# Power_Board.net
KiCad netlist of a schematic drawn in Altium Designer
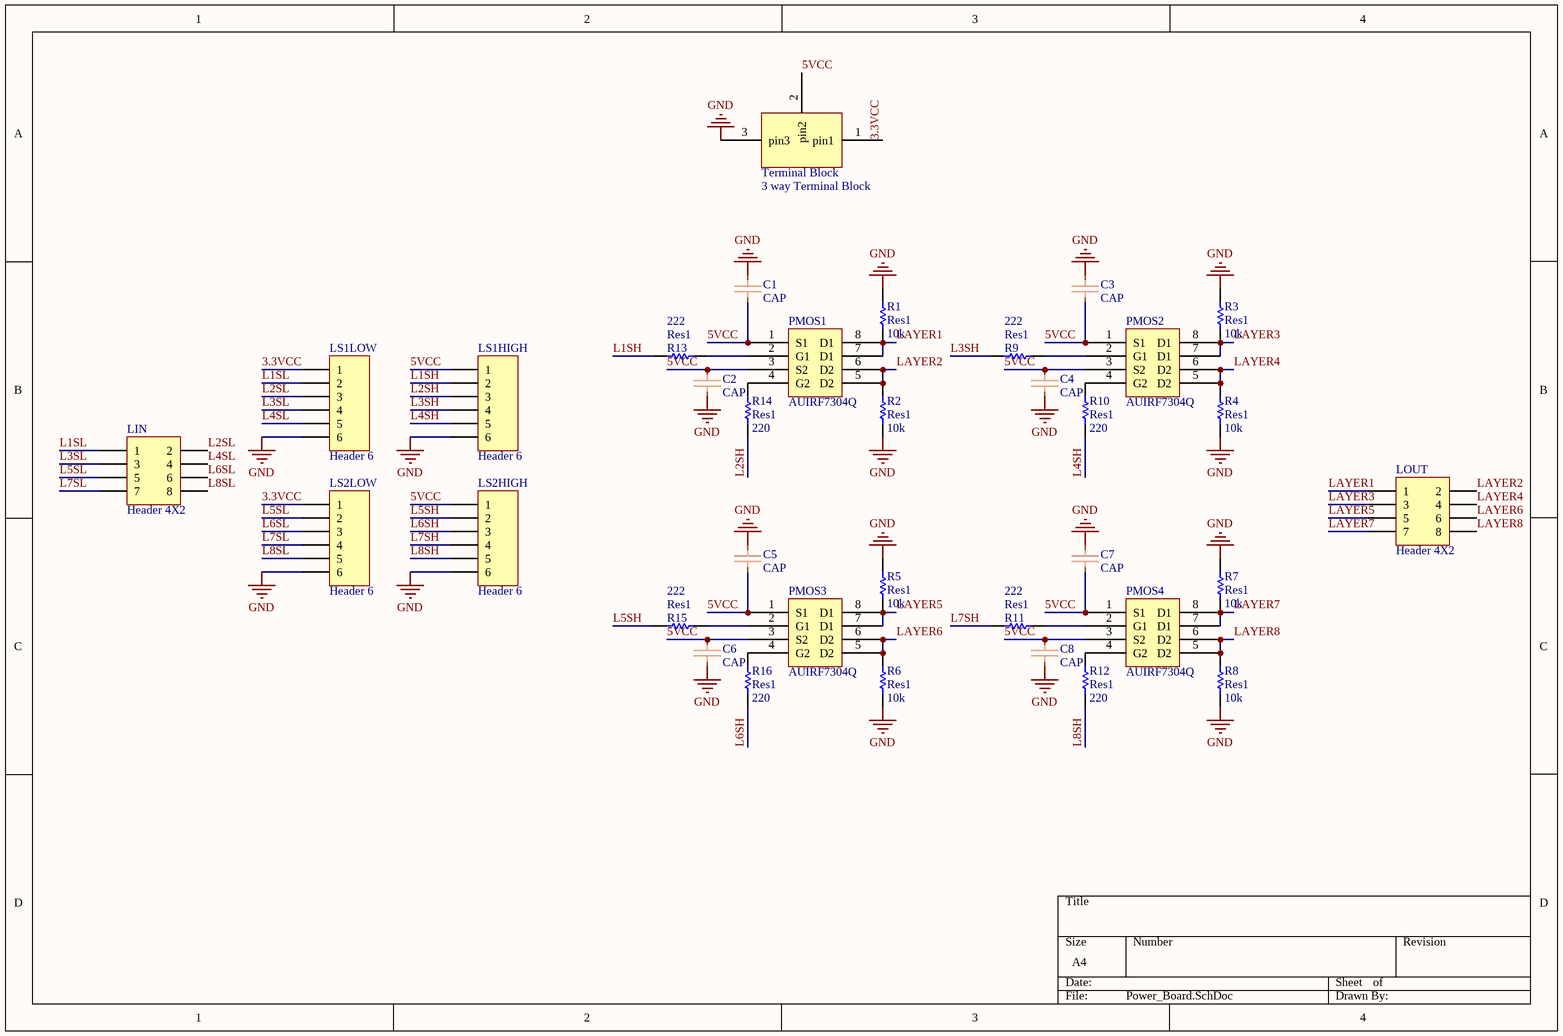
[diagram p0: Power_Board.SchDoc]

(export (version "E")
  (design (tool "Eeschema 10.0.6"))
  (components
    (comp (ref "C1")
      (value "CAP")
      (footprint "RAD0.2A")
      (description "Capacitor")
      (libsource (lib "KBsch01") (part "CAP"))
    )
    (comp (ref "C2")
      (value "CAP")
      (footprint "RAD0.2A")
      (description "Capacitor")
      (libsource (lib "KBsch01") (part "CAP"))
    )
    (comp (ref "C3")
      (value "CAP")
      (footprint "RAD0.2A")
      (description "Capacitor")
      (libsource (lib "KBsch01") (part "CAP"))
    )
    (comp (ref "C4")
      (value "CAP")
      (footprint "RAD0.2A")
      (description "Capacitor")
      (libsource (lib "KBsch01") (part "CAP"))
    )
    (comp (ref "C5")
      (value "CAP")
      (footprint "RAD0.2A")
      (description "Capacitor")
      (libsource (lib "KBsch01") (part "CAP"))
    )
    (comp (ref "C6")
      (value "CAP")
      (footprint "RAD0.2A")
      (description "Capacitor")
      (libsource (lib "KBsch01") (part "CAP"))
    )
    (comp (ref "C7")
      (value "CAP")
      (footprint "RAD0.2A")
      (description "Capacitor")
      (libsource (lib "KBsch01") (part "CAP"))
    )
    (comp (ref "C8")
      (value "CAP")
      (footprint "RAD0.2A")
      (description "Capacitor")
      (libsource (lib "KBsch01") (part "CAP"))
    )
    (comp (ref "LIN")
      (value "Header 4X2")
      (footprint "HDR2X4")
      (description "Header, 4-Pin, Dual row")
      (fields (field (name "PUBLISHER") "Altium Limited"))
      (libsource (lib "Miscellaneous Connectors") (part "Header 4X2"))
    )
    (comp (ref "LOUT")
      (value "Header 4X2")
      (footprint "HDR2X4")
      (description "Header, 4-Pin, Dual row")
      (fields (field (name "PUBLISHER") "Altium Limited"))
      (libsource (lib "Miscellaneous Connectors") (part "Header 4X2"))
    )
    (comp (ref "LS1HIGH")
      (value "Header 6")
      (footprint "HDR1X6")
      (description "Header, 6-Pin")
      (fields (field (name "PUBLISHER") "Altium Limited"))
      (libsource (lib "Miscellaneous Connectors") (part "Header 6"))
    )
    (comp (ref "LS1LOW")
      (value "Header 6")
      (footprint "HDR1X6")
      (description "Header, 6-Pin")
      (fields (field (name "PUBLISHER") "Altium Limited"))
      (libsource (lib "Miscellaneous Connectors") (part "Header 6"))
    )
    (comp (ref "LS2HIGH")
      (value "Header 6")
      (footprint "HDR1X6")
      (description "Header, 6-Pin")
      (fields (field (name "PUBLISHER") "Altium Limited"))
      (libsource (lib "Miscellaneous Connectors") (part "Header 6"))
    )
    (comp (ref "LS2LOW")
      (value "Header 6")
      (footprint "HDR1X6")
      (description "Header, 6-Pin")
      (fields (field (name "PUBLISHER") "Altium Limited"))
      (libsource (lib "Miscellaneous Connectors") (part "Header 6"))
    )
    (comp (ref "PMOS1")
      (value "AUIRF7304Q")
      (footprint "AUIRF7304Q")
      (libsource (lib "AUIRF7304Q") (part "Component_1"))
    )
    (comp (ref "PMOS2")
      (value "AUIRF7304Q")
      (footprint "AUIRF7304Q")
      (libsource (lib "AUIRF7304Q") (part "Component_1"))
    )
    (comp (ref "PMOS3")
      (value "AUIRF7304Q")
      (footprint "AUIRF7304Q")
      (libsource (lib "AUIRF7304Q") (part "Component_1"))
    )
    (comp (ref "PMOS4")
      (value "AUIRF7304Q")
      (footprint "AUIRF7304Q")
      (libsource (lib "AUIRF7304Q") (part "Component_1"))
    )
    (comp (ref "R1")
      (value "Res1")
      (footprint "AXIAL0.4")
      (description "Resistor")
      (fields (field (name "ALTIUM_VALUE") "10k") (field (name "PUBLISHER") "Altium Limited"))
      (libsource (lib "Miscellaneous Devices") (part "Res1"))
    )
    (comp (ref "R2")
      (value "Res1")
      (footprint "AXIAL0.4")
      (description "Resistor")
      (fields (field (name "ALTIUM_VALUE") "10k") (field (name "PUBLISHER") "Altium Limited"))
      (libsource (lib "Miscellaneous Devices") (part "Res1"))
    )
    (comp (ref "R3")
      (value "Res1")
      (footprint "AXIAL0.4")
      (description "Resistor")
      (fields (field (name "ALTIUM_VALUE") "10k") (field (name "PUBLISHER") "Altium Limited"))
      (libsource (lib "Miscellaneous Devices") (part "Res1"))
    )
    (comp (ref "R4")
      (value "Res1")
      (footprint "AXIAL0.4")
      (description "Resistor")
      (fields (field (name "ALTIUM_VALUE") "10k") (field (name "PUBLISHER") "Altium Limited"))
      (libsource (lib "Miscellaneous Devices") (part "Res1"))
    )
    (comp (ref "R5")
      (value "Res1")
      (footprint "AXIAL0.4")
      (description "Resistor")
      (fields (field (name "ALTIUM_VALUE") "10k") (field (name "PUBLISHER") "Altium Limited"))
      (libsource (lib "Miscellaneous Devices") (part "Res1"))
    )
    (comp (ref "R6")
      (value "Res1")
      (footprint "AXIAL0.4")
      (description "Resistor")
      (fields (field (name "ALTIUM_VALUE") "10k") (field (name "PUBLISHER") "Altium Limited"))
      (libsource (lib "Miscellaneous Devices") (part "Res1"))
    )
    (comp (ref "R7")
      (value "Res1")
      (footprint "AXIAL0.4")
      (description "Resistor")
      (fields (field (name "ALTIUM_VALUE") "10k") (field (name "PUBLISHER") "Altium Limited"))
      (libsource (lib "Miscellaneous Devices") (part "Res1"))
    )
    (comp (ref "R8")
      (value "Res1")
      (footprint "AXIAL0.4")
      (description "Resistor")
      (fields (field (name "ALTIUM_VALUE") "10k") (field (name "PUBLISHER") "Altium Limited"))
      (libsource (lib "Miscellaneous Devices") (part "Res1"))
    )
    (comp (ref "R9")
      (value "Res1")
      (footprint "AXIAL0.4")
      (description "Resistor")
      (fields (field (name "ALTIUM_VALUE") "222") (field (name "PUBLISHER") "Altium Limited"))
      (libsource (lib "Miscellaneous Devices") (part "Res1"))
    )
    (comp (ref "R10")
      (value "Res1")
      (footprint "AXIAL0.4")
      (description "Resistor")
      (fields (field (name "ALTIUM_VALUE") "220") (field (name "PUBLISHER") "Altium Limited"))
      (libsource (lib "Miscellaneous Devices") (part "Res1"))
    )
    (comp (ref "R11")
      (value "Res1")
      (footprint "AXIAL0.4")
      (description "Resistor")
      (fields (field (name "ALTIUM_VALUE") "222") (field (name "PUBLISHER") "Altium Limited"))
      (libsource (lib "Miscellaneous Devices") (part "Res1"))
    )
    (comp (ref "R12")
      (value "Res1")
      (footprint "AXIAL0.4")
      (description "Resistor")
      (fields (field (name "ALTIUM_VALUE") "220") (field (name "PUBLISHER") "Altium Limited"))
      (libsource (lib "Miscellaneous Devices") (part "Res1"))
    )
    (comp (ref "R13")
      (value "Res1")
      (footprint "AXIAL0.4")
      (description "Resistor")
      (fields (field (name "ALTIUM_VALUE") "222") (field (name "PUBLISHER") "Altium Limited"))
      (libsource (lib "Miscellaneous Devices") (part "Res1"))
    )
    (comp (ref "R14")
      (value "Res1")
      (footprint "AXIAL0.4")
      (description "Resistor")
      (fields (field (name "ALTIUM_VALUE") "220") (field (name "PUBLISHER") "Altium Limited"))
      (libsource (lib "Miscellaneous Devices") (part "Res1"))
    )
    (comp (ref "R15")
      (value "Res1")
      (footprint "AXIAL0.4")
      (description "Resistor")
      (fields (field (name "ALTIUM_VALUE") "222") (field (name "PUBLISHER") "Altium Limited"))
      (libsource (lib "Miscellaneous Devices") (part "Res1"))
    )
    (comp (ref "R16")
      (value "Res1")
      (footprint "AXIAL0.4")
      (description "Resistor")
      (fields (field (name "ALTIUM_VALUE") "220") (field (name "PUBLISHER") "Altium Limited"))
      (libsource (lib "Miscellaneous Devices") (part "Res1"))
    )
    (comp (ref "Terminal Block")
      (value "3 way Terminal Block")
      (footprint "PCTB3N")
      (libsource (lib "Terminal Block") (part "Component_1"))
    )
  )
  (nets
    (net (code "1") (name "/3.3VCC") (class "Default")
      (node (ref "LS1LOW") (pin "1") (pinfunction "1_1") (pintype "passive"))
      (node (ref "LS2LOW") (pin "1") (pinfunction "1_1") (pintype "passive"))
      (node (ref "Terminal Block") (pin "1") (pinfunction "pin1_1") (pintype "passive"))
    )
    (net (code "2") (name "/5VCC") (class "Default")
      (node (ref "C1") (pin "2") (pinfunction "N/A_2") (pintype "passive"))
      (node (ref "C2") (pin "1") (pinfunction "N/A_1") (pintype "passive"))
      (node (ref "C3") (pin "2") (pinfunction "N/A_2") (pintype "passive"))
      (node (ref "C4") (pin "1") (pinfunction "N/A_1") (pintype "passive"))
      (node (ref "C5") (pin "2") (pinfunction "N/A_2") (pintype "passive"))
      (node (ref "C6") (pin "1") (pinfunction "N/A_1") (pintype "passive"))
      (node (ref "C7") (pin "2") (pinfunction "N/A_2") (pintype "passive"))
      (node (ref "C8") (pin "1") (pinfunction "N/A_1") (pintype "passive"))
      (node (ref "LS1HIGH") (pin "1") (pinfunction "1_1") (pintype "passive"))
      (node (ref "LS2HIGH") (pin "1") (pinfunction "1_1") (pintype "passive"))
      (node (ref "PMOS1") (pin "1") (pinfunction "S1_1") (pintype "passive"))
      (node (ref "PMOS1") (pin "3") (pinfunction "S2_3") (pintype "passive"))
      (node (ref "PMOS2") (pin "1") (pinfunction "S1_1") (pintype "passive"))
      (node (ref "PMOS2") (pin "3") (pinfunction "S2_3") (pintype "passive"))
      (node (ref "PMOS3") (pin "1") (pinfunction "S1_1") (pintype "passive"))
      (node (ref "PMOS3") (pin "3") (pinfunction "S2_3") (pintype "passive"))
      (node (ref "PMOS4") (pin "1") (pinfunction "S1_1") (pintype "passive"))
      (node (ref "PMOS4") (pin "3") (pinfunction "S2_3") (pintype "passive"))
      (node (ref "Terminal Block") (pin "2") (pinfunction "pin2_2") (pintype "passive"))
    )
    (net (code "3") (name "/L1SH") (class "Default")
      (node (ref "LS1HIGH") (pin "2") (pinfunction "2_2") (pintype "passive"))
      (node (ref "R13") (pin "1") (pinfunction "1_1") (pintype "passive"))
    )
    (net (code "4") (name "/L1SL") (class "Default")
      (node (ref "LIN") (pin "1") (pinfunction "1_1") (pintype "passive"))
      (node (ref "LS1LOW") (pin "2") (pinfunction "2_2") (pintype "passive"))
    )
    (net (code "5") (name "/L2SH") (class "Default")
      (node (ref "LS1HIGH") (pin "3") (pinfunction "3_3") (pintype "passive"))
      (node (ref "R14") (pin "1") (pinfunction "1_1") (pintype "passive"))
    )
    (net (code "6") (name "/L2SL") (class "Default")
      (node (ref "LIN") (pin "2") (pinfunction "2_2") (pintype "passive"))
      (node (ref "LS1LOW") (pin "3") (pinfunction "3_3") (pintype "passive"))
    )
    (net (code "7") (name "/L3SH") (class "Default")
      (node (ref "LS1HIGH") (pin "4") (pinfunction "4_4") (pintype "passive"))
      (node (ref "R9") (pin "1") (pinfunction "1_1") (pintype "passive"))
    )
    (net (code "8") (name "/L3SL") (class "Default")
      (node (ref "LIN") (pin "3") (pinfunction "3_3") (pintype "passive"))
      (node (ref "LS1LOW") (pin "4") (pinfunction "4_4") (pintype "passive"))
    )
    (net (code "9") (name "/L4SH") (class "Default")
      (node (ref "LS1HIGH") (pin "5") (pinfunction "5_5") (pintype "passive"))
      (node (ref "R10") (pin "1") (pinfunction "1_1") (pintype "passive"))
    )
    (net (code "10") (name "/L4SL") (class "Default")
      (node (ref "LIN") (pin "4") (pinfunction "4_4") (pintype "passive"))
      (node (ref "LS1LOW") (pin "5") (pinfunction "5_5") (pintype "passive"))
    )
    (net (code "11") (name "/L5SH") (class "Default")
      (node (ref "LS2HIGH") (pin "2") (pinfunction "2_2") (pintype "passive"))
      (node (ref "R15") (pin "1") (pinfunction "1_1") (pintype "passive"))
    )
    (net (code "12") (name "/L5SL") (class "Default")
      (node (ref "LIN") (pin "5") (pinfunction "5_5") (pintype "passive"))
      (node (ref "LS2LOW") (pin "2") (pinfunction "2_2") (pintype "passive"))
    )
    (net (code "13") (name "/L6SH") (class "Default")
      (node (ref "LS2HIGH") (pin "3") (pinfunction "3_3") (pintype "passive"))
      (node (ref "R16") (pin "1") (pinfunction "1_1") (pintype "passive"))
    )
    (net (code "14") (name "/L6SL") (class "Default")
      (node (ref "LIN") (pin "6") (pinfunction "6_6") (pintype "passive"))
      (node (ref "LS2LOW") (pin "3") (pinfunction "3_3") (pintype "passive"))
    )
    (net (code "15") (name "/L7SH") (class "Default")
      (node (ref "LS2HIGH") (pin "4") (pinfunction "4_4") (pintype "passive"))
      (node (ref "R11") (pin "1") (pinfunction "1_1") (pintype "passive"))
    )
    (net (code "16") (name "/L7SL") (class "Default")
      (node (ref "LIN") (pin "7") (pinfunction "7_7") (pintype "passive"))
      (node (ref "LS2LOW") (pin "4") (pinfunction "4_4") (pintype "passive"))
    )
    (net (code "17") (name "/L8SH") (class "Default")
      (node (ref "LS2HIGH") (pin "5") (pinfunction "5_5") (pintype "passive"))
      (node (ref "R12") (pin "1") (pinfunction "1_1") (pintype "passive"))
    )
    (net (code "18") (name "/L8SL") (class "Default")
      (node (ref "LIN") (pin "8") (pinfunction "8_8") (pintype "passive"))
      (node (ref "LS2LOW") (pin "5") (pinfunction "5_5") (pintype "passive"))
    )
    (net (code "19") (name "/LAYER1") (class "Default")
      (node (ref "LOUT") (pin "1") (pinfunction "1_1") (pintype "passive"))
      (node (ref "PMOS1") (pin "7") (pinfunction "D1_7") (pintype "passive"))
      (node (ref "PMOS1") (pin "8") (pinfunction "D1_8") (pintype "passive"))
      (node (ref "R1") (pin "2") (pinfunction "2_2") (pintype "passive"))
    )
    (net (code "20") (name "/LAYER2") (class "Default")
      (node (ref "LOUT") (pin "2") (pinfunction "2_2") (pintype "passive"))
      (node (ref "PMOS1") (pin "5") (pinfunction "D2_5") (pintype "passive"))
      (node (ref "PMOS1") (pin "6") (pinfunction "D2_6") (pintype "passive"))
      (node (ref "R2") (pin "1") (pinfunction "1_1") (pintype "passive"))
    )
    (net (code "21") (name "/LAYER3") (class "Default")
      (node (ref "LOUT") (pin "3") (pinfunction "3_3") (pintype "passive"))
      (node (ref "PMOS2") (pin "7") (pinfunction "D1_7") (pintype "passive"))
      (node (ref "PMOS2") (pin "8") (pinfunction "D1_8") (pintype "passive"))
      (node (ref "R3") (pin "2") (pinfunction "2_2") (pintype "passive"))
    )
    (net (code "22") (name "/LAYER4") (class "Default")
      (node (ref "LOUT") (pin "4") (pinfunction "4_4") (pintype "passive"))
      (node (ref "PMOS2") (pin "5") (pinfunction "D2_5") (pintype "passive"))
      (node (ref "PMOS2") (pin "6") (pinfunction "D2_6") (pintype "passive"))
      (node (ref "R4") (pin "1") (pinfunction "1_1") (pintype "passive"))
    )
    (net (code "23") (name "/LAYER5") (class "Default")
      (node (ref "LOUT") (pin "5") (pinfunction "5_5") (pintype "passive"))
      (node (ref "PMOS3") (pin "7") (pinfunction "D1_7") (pintype "passive"))
      (node (ref "PMOS3") (pin "8") (pinfunction "D1_8") (pintype "passive"))
      (node (ref "R5") (pin "2") (pinfunction "2_2") (pintype "passive"))
    )
    (net (code "24") (name "/LAYER6") (class "Default")
      (node (ref "LOUT") (pin "6") (pinfunction "6_6") (pintype "passive"))
      (node (ref "PMOS3") (pin "5") (pinfunction "D2_5") (pintype "passive"))
      (node (ref "PMOS3") (pin "6") (pinfunction "D2_6") (pintype "passive"))
      (node (ref "R6") (pin "1") (pinfunction "1_1") (pintype "passive"))
    )
    (net (code "25") (name "/LAYER7") (class "Default")
      (node (ref "LOUT") (pin "7") (pinfunction "7_7") (pintype "passive"))
      (node (ref "PMOS4") (pin "7") (pinfunction "D1_7") (pintype "passive"))
      (node (ref "PMOS4") (pin "8") (pinfunction "D1_8") (pintype "passive"))
      (node (ref "R7") (pin "2") (pinfunction "2_2") (pintype "passive"))
    )
    (net (code "26") (name "/LAYER8") (class "Default")
      (node (ref "LOUT") (pin "8") (pinfunction "8_8") (pintype "passive"))
      (node (ref "PMOS4") (pin "5") (pinfunction "D2_5") (pintype "passive"))
      (node (ref "PMOS4") (pin "6") (pinfunction "D2_6") (pintype "passive"))
      (node (ref "R8") (pin "1") (pinfunction "1_1") (pintype "passive"))
    )
    (net (code "27") (name "GND") (class "Default")
      (node (ref "C1") (pin "1") (pinfunction "N/A_1") (pintype "passive"))
      (node (ref "C2") (pin "2") (pinfunction "N/A_2") (pintype "passive"))
      (node (ref "C3") (pin "1") (pinfunction "N/A_1") (pintype "passive"))
      (node (ref "C4") (pin "2") (pinfunction "N/A_2") (pintype "passive"))
      (node (ref "C5") (pin "1") (pinfunction "N/A_1") (pintype "passive"))
      (node (ref "C6") (pin "2") (pinfunction "N/A_2") (pintype "passive"))
      (node (ref "C7") (pin "1") (pinfunction "N/A_1") (pintype "passive"))
      (node (ref "C8") (pin "2") (pinfunction "N/A_2") (pintype "passive"))
      (node (ref "LS1HIGH") (pin "6") (pinfunction "6_6") (pintype "passive"))
      (node (ref "LS1LOW") (pin "6") (pinfunction "6_6") (pintype "passive"))
      (node (ref "LS2HIGH") (pin "6") (pinfunction "6_6") (pintype "passive"))
      (node (ref "LS2LOW") (pin "6") (pinfunction "6_6") (pintype "passive"))
      (node (ref "R1") (pin "1") (pinfunction "1_1") (pintype "passive"))
      (node (ref "R2") (pin "2") (pinfunction "2_2") (pintype "passive"))
      (node (ref "R3") (pin "1") (pinfunction "1_1") (pintype "passive"))
      (node (ref "R4") (pin "2") (pinfunction "2_2") (pintype "passive"))
      (node (ref "R5") (pin "1") (pinfunction "1_1") (pintype "passive"))
      (node (ref "R6") (pin "2") (pinfunction "2_2") (pintype "passive"))
      (node (ref "R7") (pin "1") (pinfunction "1_1") (pintype "passive"))
      (node (ref "R8") (pin "2") (pinfunction "2_2") (pintype "passive"))
      (node (ref "Terminal Block") (pin "3") (pinfunction "pin3_3") (pintype "passive"))
    )
    (net (code "28") (name "Net-(PMOS1-G1)") (class "Default")
      (node (ref "PMOS1") (pin "2") (pinfunction "G1_2") (pintype "passive"))
      (node (ref "R13") (pin "2") (pinfunction "2_2") (pintype "passive"))
    )
    (net (code "29") (name "Net-(PMOS1-G2)") (class "Default")
      (node (ref "PMOS1") (pin "4") (pinfunction "G2_4") (pintype "passive"))
      (node (ref "R14") (pin "2") (pinfunction "2_2") (pintype "passive"))
    )
    (net (code "30") (name "Net-(PMOS2-G1)") (class "Default")
      (node (ref "PMOS2") (pin "2") (pinfunction "G1_2") (pintype "passive"))
      (node (ref "R9") (pin "2") (pinfunction "2_2") (pintype "passive"))
    )
    (net (code "31") (name "Net-(PMOS2-G2)") (class "Default")
      (node (ref "PMOS2") (pin "4") (pinfunction "G2_4") (pintype "passive"))
      (node (ref "R10") (pin "2") (pinfunction "2_2") (pintype "passive"))
    )
    (net (code "32") (name "Net-(PMOS3-G1)") (class "Default")
      (node (ref "PMOS3") (pin "2") (pinfunction "G1_2") (pintype "passive"))
      (node (ref "R15") (pin "2") (pinfunction "2_2") (pintype "passive"))
    )
    (net (code "33") (name "Net-(PMOS3-G2)") (class "Default")
      (node (ref "PMOS3") (pin "4") (pinfunction "G2_4") (pintype "passive"))
      (node (ref "R16") (pin "2") (pinfunction "2_2") (pintype "passive"))
    )
    (net (code "34") (name "Net-(PMOS4-G1)") (class "Default")
      (node (ref "PMOS4") (pin "2") (pinfunction "G1_2") (pintype "passive"))
      (node (ref "R11") (pin "2") (pinfunction "2_2") (pintype "passive"))
    )
    (net (code "35") (name "Net-(PMOS4-G2)") (class "Default")
      (node (ref "PMOS4") (pin "4") (pinfunction "G2_4") (pintype "passive"))
      (node (ref "R12") (pin "2") (pinfunction "2_2") (pintype "passive"))
    )
  )
)
